# obc-v2_CM4-FUNCTION.net
KiCad netlist of a schematic drawn in Altium Designer
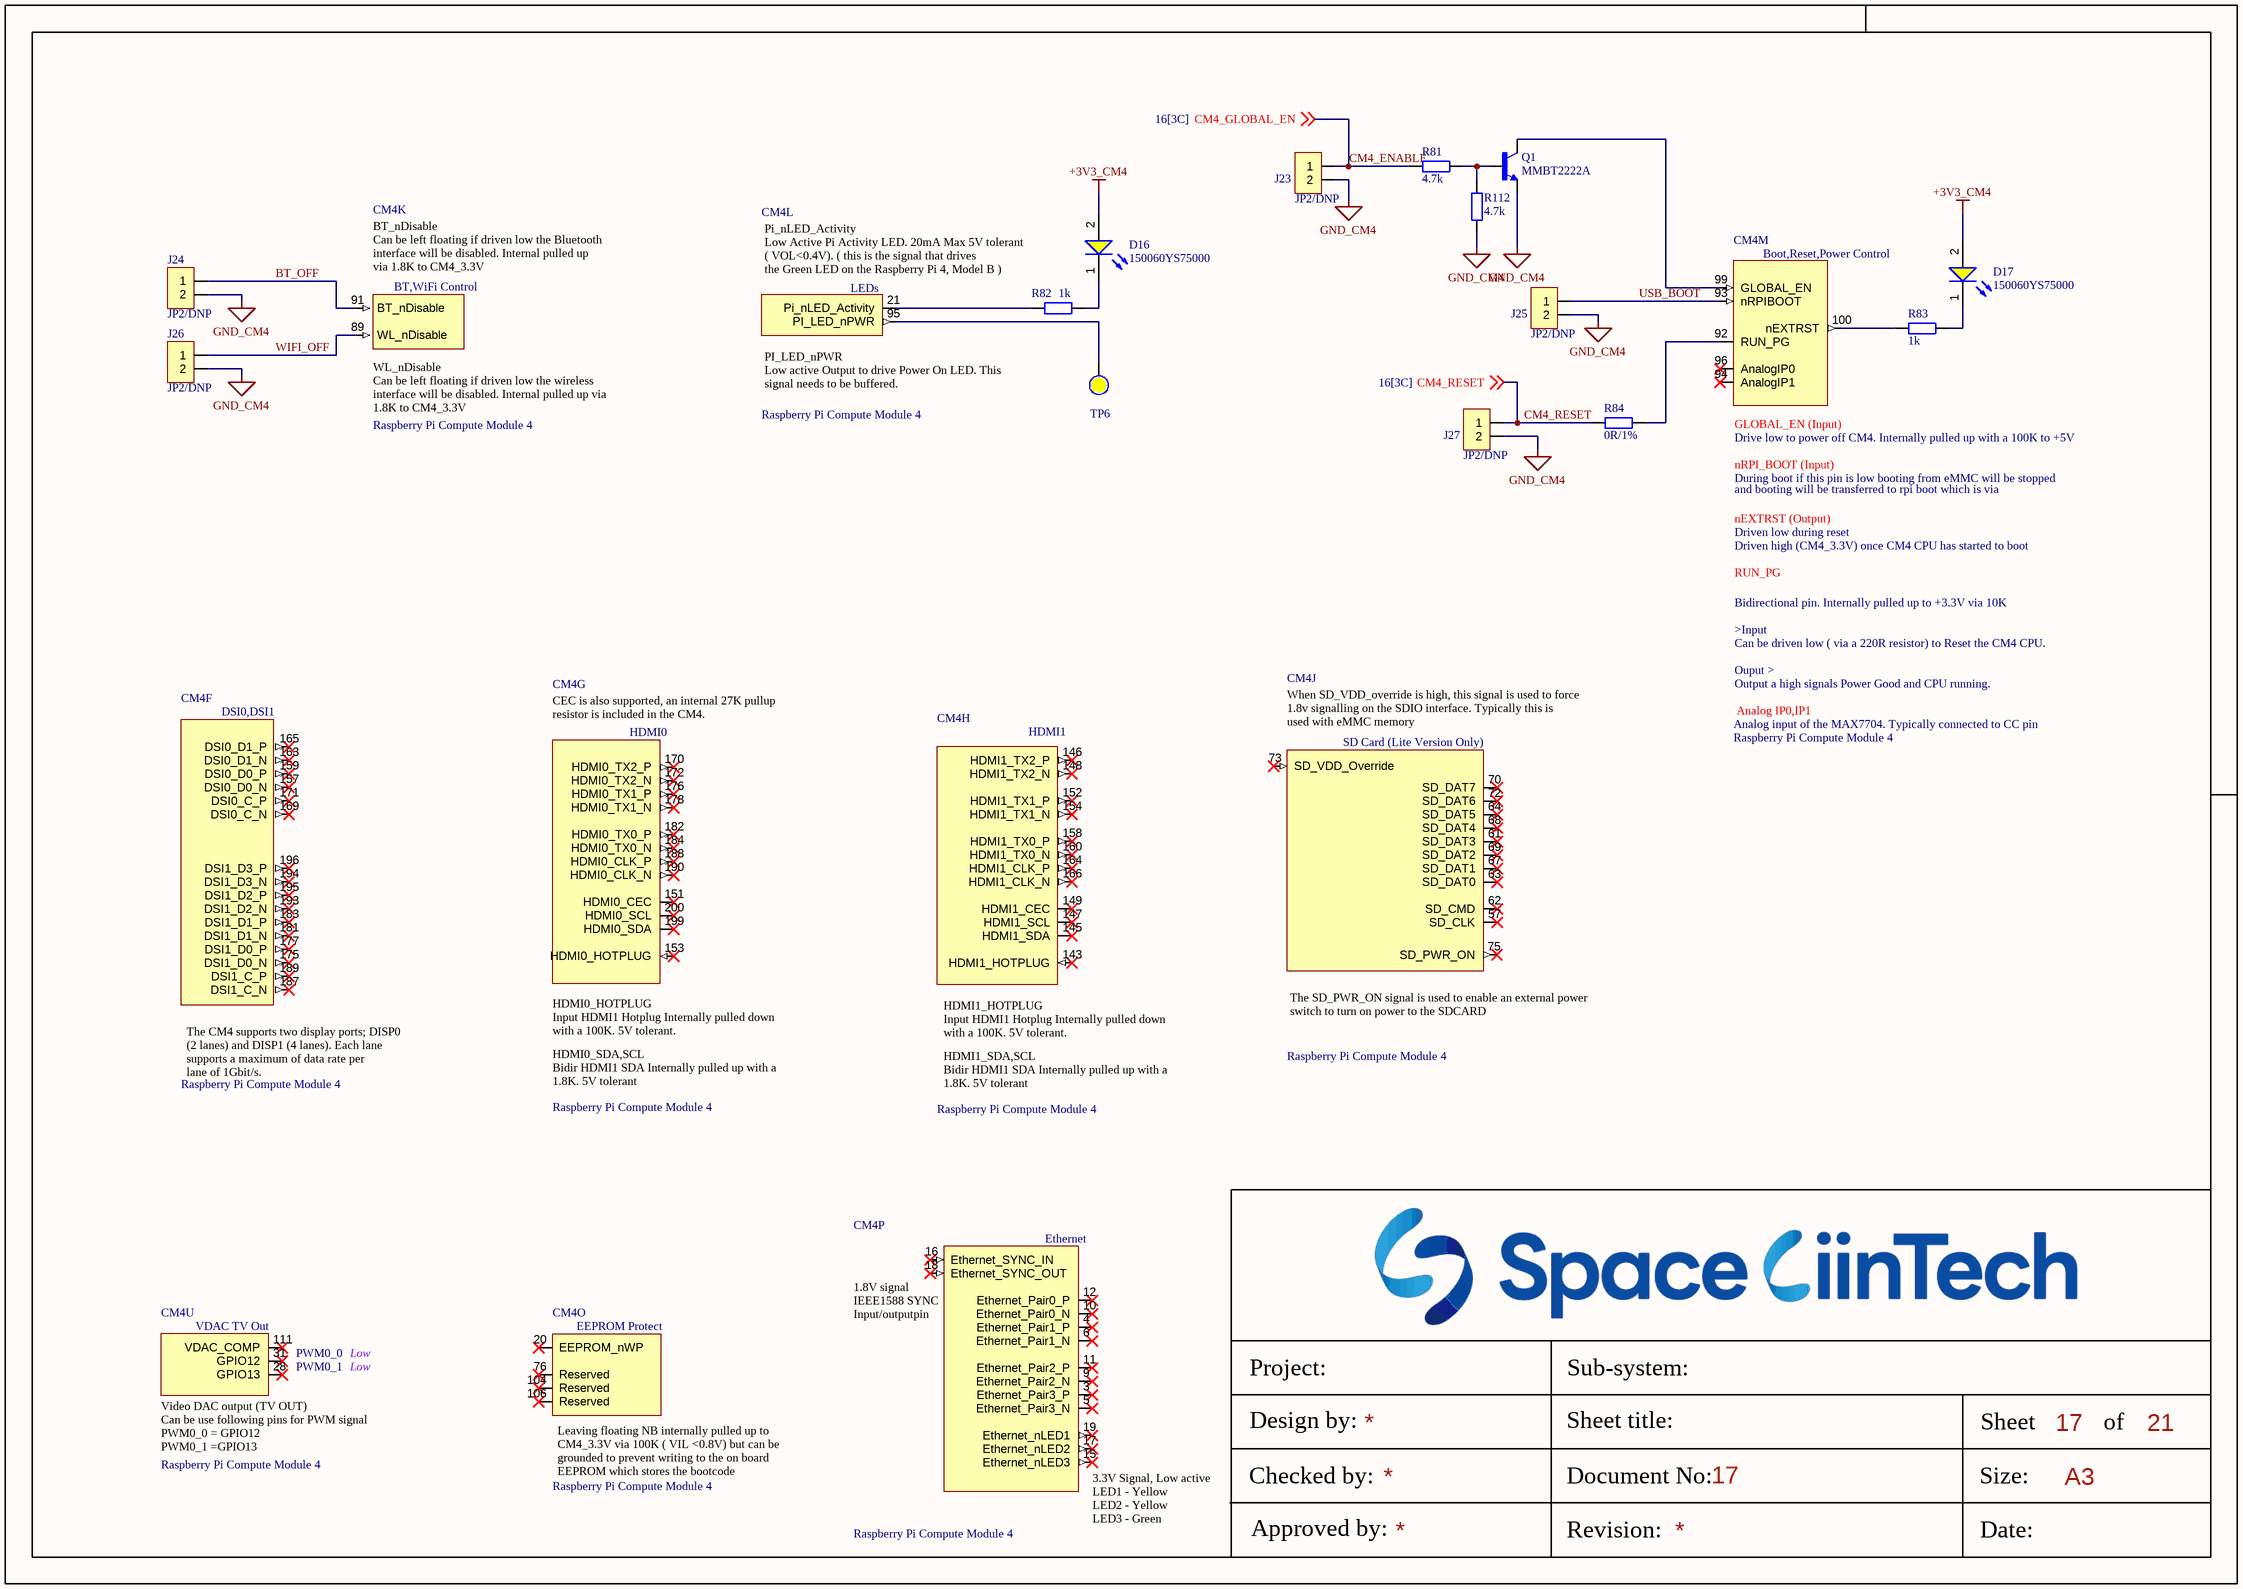
[diagram p0: obc-v2_CM4-FUNCTION.SchDoc]

(export (version "E")
  (design (tool "Eeschema 10.0.6"))
  (components
    (comp (ref "CM4")
      (value "Raspberry Pi Compute Module 4")
      (footprint "CM4-DF40HC(3.0)-100DS-0.4v_3mm_1.5mm")
      (description "Raspberry Pi Compute Module 4 by Amornthep Phunsin")
      (libsource (lib "CM4") (part "CM4"))
    )
    (comp (ref "D16")
      (value "150060YS75000")
      (footprint "WL-SMCW_0603_150060xx75000")
      (description "LED YELLOW CLEAR 0603 SMD")
      (libsource (lib "Altium Content Vault") (part "LED_Yellow_2A-1K"))
    )
    (comp (ref "D17")
      (value "150060YS75000")
      (footprint "WL-SMCW_0603_150060xx75000")
      (description "LED YELLOW CLEAR 0603 SMD")
      (libsource (lib "Altium Content Vault") (part "LED_Yellow_2A-1K"))
    )
    (comp (ref "J23")
      (value "JP2/DNP")
      (footprint "JP2-D1T")
      (description "WR-PHD 2.54 mm Angled Socket Header")
      (fields
        (field (name "MANUFACTURER") "Würth Elektronik eiSos GmbH")
        (field (name "PARTNO") "613002143121")
        (field (name "CREATED BY") "Karrer Zheng")
      )
      (libsource (lib "TechMT.VN_Lib") (part "JP2"))
    )
    (comp (ref "J24")
      (value "JP2/DNP")
      (footprint "JP2-D1T")
      (description "WR-PHD 2.54 mm Angled Socket Header")
      (fields
        (field (name "MANUFACTURER") "Würth Elektronik eiSos GmbH")
        (field (name "PARTNO") "613002143121")
        (field (name "CREATED BY") "Karrer Zheng")
      )
      (libsource (lib "TechMT.VN_Lib") (part "JP2"))
    )
    (comp (ref "J25")
      (value "JP2/DNP")
      (footprint "JP2-D1T")
      (description "WR-PHD 2.54 mm Angled Socket Header")
      (fields
        (field (name "MANUFACTURER") "Würth Elektronik eiSos GmbH")
        (field (name "PARTNO") "613002143121")
        (field (name "CREATED BY") "Karrer Zheng")
      )
      (libsource (lib "TechMT.VN_Lib") (part "JP2"))
    )
    (comp (ref "J26")
      (value "JP2/DNP")
      (footprint "JP2-D1T")
      (description "WR-PHD 2.54 mm Angled Socket Header")
      (fields
        (field (name "MANUFACTURER") "Würth Elektronik eiSos GmbH")
        (field (name "PARTNO") "613002143121")
        (field (name "CREATED BY") "Karrer Zheng")
      )
      (libsource (lib "TechMT.VN_Lib") (part "JP2"))
    )
    (comp (ref "J27")
      (value "JP2/DNP")
      (footprint "JP2-D1T")
      (description "WR-PHD 2.54 mm Angled Socket Header")
      (fields
        (field (name "MANUFACTURER") "Würth Elektronik eiSos GmbH")
        (field (name "PARTNO") "613002143121")
        (field (name "CREATED BY") "Karrer Zheng")
      )
      (libsource (lib "TechMT.VN_Lib") (part "JP2"))
    )
    (comp (ref "Q1")
      (value "MMBT2222A")
      (footprint "SOT95P240X120-3N")
      (description "BJT, SOT-23, 40V, 600mA, NPN, 0.25W, 150°C")
      (fields (field (name "MF") "Diotec Semiconductor"))
      (libsource (lib "obc_ver2") (part "MMBT2222A"))
    )
    (comp (ref "R81")
      (value "4.7k")
      (footprint "RES_C_1608X60")
      (description "RES")
      (libsource (lib "Altium_Lib_by_KhueNguyenCreator") (part "Tro 0603 1% 10k"))
    )
    (comp (ref "R82")
      (value "1k")
      (footprint "RES_C_1608X60")
      (description "RES")
      (libsource (lib "Altium_Lib_by_KhueNguyenCreator") (part "Tro 0603 1% 10k"))
    )
    (comp (ref "R83")
      (value "1k")
      (footprint "RES_C_1608X60")
      (description "RES")
      (libsource (lib "Altium_Lib_by_KhueNguyenCreator") (part "Tro 0603 1% 10k"))
    )
    (comp (ref "R84")
      (value "0R/1%")
      (footprint "RES_C_1608X60")
      (description "RES")
      (libsource (lib "Altium_Lib_by_KhueNguyenCreator") (part "Tro 0603 1% 10k"))
    )
    (comp (ref "R112")
      (value "4.7k")
      (footprint "RES_C_1608X60")
      (description "RES")
      (libsource (lib "Altium_Lib_by_KhueNguyenCreator") (part "Tro 0603 1% 10k"))
    )
    (comp (ref "TP6")
      (value "~")
      (footprint "Test Point 1 Side")
      (description "Test Point")
      (libsource (lib "BYTECH_HW_LIB_2019 (1)") (part "Test Point"))
    )
  )
  (nets
    (net (code "1") (name "+3V3_CM4") (class "Default")
      (node (ref "D16") (pin "2") (pinfunction "A_2") (pintype "passive"))
      (node (ref "D17") (pin "2") (pinfunction "A_2") (pintype "passive"))
    )
    (net (code "2") (name "/BT_OFF") (class "Default")
      (node (ref "CM4") (pin "91") (pinfunction "BT_nDisable_91") (pintype "input"))
      (node (ref "J24") (pin "1") (pinfunction "1_1") (pintype "passive"))
    )
    (net (code "3") (name "/USB_BOOT") (class "Default")
      (node (ref "CM4") (pin "93") (pinfunction "nRPIBOOT_93") (pintype "input"))
      (node (ref "J25") (pin "1") (pinfunction "1_1") (pintype "passive"))
    )
    (net (code "4") (name "/WIFI_OFF") (class "Default")
      (node (ref "CM4") (pin "89") (pinfunction "WL_nDisable_89") (pintype "input"))
      (node (ref "J26") (pin "1") (pinfunction "1_1") (pintype "passive"))
    )
    (net (code "5") (name "CM4_GLOBAL_EN") (class "Default")
      (node (ref "J23") (pin "1") (pinfunction "1_1") (pintype "passive"))
      (node (ref "R81") (pin "2") (pinfunction "2_2") (pintype "passive"))
    )
    (net (code "6") (name "CM4_RESET") (class "Default")
      (node (ref "J27") (pin "1") (pinfunction "1_1") (pintype "passive"))
      (node (ref "R84") (pin "2") (pinfunction "2_2") (pintype "passive"))
    )
    (net (code "7") (name "GND_CM4") (class "Default")
      (node (ref "J23") (pin "2") (pinfunction "2_2") (pintype "passive"))
      (node (ref "J24") (pin "2") (pinfunction "2_2") (pintype "passive"))
      (node (ref "J25") (pin "2") (pinfunction "2_2") (pintype "passive"))
      (node (ref "J26") (pin "2") (pinfunction "2_2") (pintype "passive"))
      (node (ref "J27") (pin "2") (pinfunction "2_2") (pintype "passive"))
      (node (ref "Q1") (pin "2") (pinfunction "E_2") (pintype "passive"))
      (node (ref "R112") (pin "2") (pinfunction "2_2") (pintype "passive"))
    )
    (net (code "8") (name "Net-(CM4L-PI_LED_nPWR)") (class "Default")
      (node (ref "CM4") (pin "95") (pinfunction "PI_LED_nPWR_95") (pintype "output"))
      (node (ref "TP6") (pin "0") (pinfunction "0_0") (pintype "passive"))
    )
    (net (code "9") (name "Net-(CM4L-Pi_nLED_Activity)") (class "Default")
      (node (ref "CM4") (pin "21") (pinfunction "Pi_nLED_Activity_21") (pintype "open_collector"))
      (node (ref "R82") (pin "2") (pinfunction "2_2") (pintype "passive"))
    )
    (net (code "10") (name "Net-(CM4M-GLOBAL_EN)") (class "Default")
      (node (ref "CM4") (pin "99") (pinfunction "GLOBAL_EN_99") (pintype "input"))
      (node (ref "Q1") (pin "3") (pinfunction "C_3") (pintype "passive"))
    )
    (net (code "11") (name "Net-(CM4M-RUN_PG)") (class "Default")
      (node (ref "CM4") (pin "92") (pinfunction "RUN_PG_92") (pintype "passive"))
      (node (ref "R84") (pin "1") (pinfunction "1_1") (pintype "passive"))
    )
    (net (code "12") (name "Net-(CM4M-nEXTRST)") (class "Default")
      (node (ref "CM4") (pin "100") (pinfunction "nEXTRST_100") (pintype "output"))
      (node (ref "R83") (pin "2") (pinfunction "2_2") (pintype "passive"))
    )
    (net (code "13") (name "Net-(D16-K)") (class "Default")
      (node (ref "D16") (pin "1") (pinfunction "K_1") (pintype "passive"))
      (node (ref "R82") (pin "1") (pinfunction "1_1") (pintype "passive"))
    )
    (net (code "14") (name "Net-(D17-K)") (class "Default")
      (node (ref "D17") (pin "1") (pinfunction "K_1") (pintype "passive"))
      (node (ref "R83") (pin "1") (pinfunction "1_1") (pintype "passive"))
    )
    (net (code "15") (name "Net-(Q1-B)") (class "Default")
      (node (ref "Q1") (pin "1") (pinfunction "B_1") (pintype "passive"))
      (node (ref "R112") (pin "1") (pinfunction "1_1") (pintype "passive"))
      (node (ref "R81") (pin "1") (pinfunction "1_1") (pintype "passive"))
    )
    (net (code "16") (name "unconnected-(CM4F-DSI0_C_N-Pad169)") (class "Default")
      (node (ref "CM4") (pin "169") (pinfunction "DSI0_C_N_169") (pintype "output+no_connect"))
    )
    (net (code "17") (name "unconnected-(CM4F-DSI0_C_P-Pad171)") (class "Default")
      (node (ref "CM4") (pin "171") (pinfunction "DSI0_C_P_171") (pintype "output+no_connect"))
    )
    (net (code "18") (name "unconnected-(CM4F-DSI0_D0_N-Pad157)") (class "Default")
      (node (ref "CM4") (pin "157") (pinfunction "DSI0_D0_N_157") (pintype "output+no_connect"))
    )
    (net (code "19") (name "unconnected-(CM4F-DSI0_D0_P-Pad159)") (class "Default")
      (node (ref "CM4") (pin "159") (pinfunction "DSI0_D0_P_159") (pintype "output+no_connect"))
    )
    (net (code "20") (name "unconnected-(CM4F-DSI0_D1_N-Pad163)") (class "Default")
      (node (ref "CM4") (pin "163") (pinfunction "DSI0_D1_N_163") (pintype "output+no_connect"))
    )
    (net (code "21") (name "unconnected-(CM4F-DSI0_D1_P-Pad165)") (class "Default")
      (node (ref "CM4") (pin "165") (pinfunction "DSI0_D1_P_165") (pintype "output+no_connect"))
    )
    (net (code "22") (name "unconnected-(CM4F-DSI1_C_N-Pad187)") (class "Default")
      (node (ref "CM4") (pin "187") (pinfunction "DSI1_C_N_187") (pintype "output+no_connect"))
    )
    (net (code "23") (name "unconnected-(CM4F-DSI1_C_P-Pad189)") (class "Default")
      (node (ref "CM4") (pin "189") (pinfunction "DSI1_C_P_189") (pintype "output+no_connect"))
    )
    (net (code "24") (name "unconnected-(CM4F-DSI1_D0_N-Pad175)") (class "Default")
      (node (ref "CM4") (pin "175") (pinfunction "DSI1_D0_N_175") (pintype "output+no_connect"))
    )
    (net (code "25") (name "unconnected-(CM4F-DSI1_D0_P-Pad177)") (class "Default")
      (node (ref "CM4") (pin "177") (pinfunction "DSI1_D0_P_177") (pintype "output+no_connect"))
    )
    (net (code "26") (name "unconnected-(CM4F-DSI1_D1_N-Pad181)") (class "Default")
      (node (ref "CM4") (pin "181") (pinfunction "DSI1_D1_N_181") (pintype "output+no_connect"))
    )
    (net (code "27") (name "unconnected-(CM4F-DSI1_D1_P-Pad183)") (class "Default")
      (node (ref "CM4") (pin "183") (pinfunction "DSI1_D1_P_183") (pintype "output+no_connect"))
    )
    (net (code "28") (name "unconnected-(CM4F-DSI1_D2_N-Pad193)") (class "Default")
      (node (ref "CM4") (pin "193") (pinfunction "DSI1_D2_N_193") (pintype "output+no_connect"))
    )
    (net (code "29") (name "unconnected-(CM4F-DSI1_D2_P-Pad195)") (class "Default")
      (node (ref "CM4") (pin "195") (pinfunction "DSI1_D2_P_195") (pintype "output+no_connect"))
    )
    (net (code "30") (name "unconnected-(CM4F-DSI1_D3_N-Pad194)") (class "Default")
      (node (ref "CM4") (pin "194") (pinfunction "DSI1_D3_N_194") (pintype "output+no_connect"))
    )
    (net (code "31") (name "unconnected-(CM4F-DSI1_D3_P-Pad196)") (class "Default")
      (node (ref "CM4") (pin "196") (pinfunction "DSI1_D3_P_196") (pintype "output+no_connect"))
    )
    (net (code "32") (name "unconnected-(CM4G-HDMI0_CEC-Pad151)") (class "Default")
      (node (ref "CM4") (pin "151") (pinfunction "HDMI0_CEC_151") (pintype "open_collector+no_connect"))
    )
    (net (code "33") (name "unconnected-(CM4G-HDMI0_CLK_N-Pad190)") (class "Default")
      (node (ref "CM4") (pin "190") (pinfunction "HDMI0_CLK_N_190") (pintype "output+no_connect"))
    )
    (net (code "34") (name "unconnected-(CM4G-HDMI0_CLK_P-Pad188)") (class "Default")
      (node (ref "CM4") (pin "188") (pinfunction "HDMI0_CLK_P_188") (pintype "output+no_connect"))
    )
    (net (code "35") (name "unconnected-(CM4G-HDMI0_HOTPLUG-Pad153)") (class "Default")
      (node (ref "CM4") (pin "153") (pinfunction "HDMI0_HOTPLUG_153") (pintype "input+no_connect"))
    )
    (net (code "36") (name "unconnected-(CM4G-HDMI0_SCL-Pad200)") (class "Default")
      (node (ref "CM4") (pin "200") (pinfunction "HDMI0_SCL_200") (pintype "open_collector+no_connect"))
    )
    (net (code "37") (name "unconnected-(CM4G-HDMI0_SDA-Pad199)") (class "Default")
      (node (ref "CM4") (pin "199") (pinfunction "HDMI0_SDA_199") (pintype "bidirectional+no_connect"))
    )
    (net (code "38") (name "unconnected-(CM4G-HDMI0_TX0_N-Pad184)") (class "Default")
      (node (ref "CM4") (pin "184") (pinfunction "HDMI0_TX0_N_184") (pintype "output+no_connect"))
    )
    (net (code "39") (name "unconnected-(CM4G-HDMI0_TX0_P-Pad182)") (class "Default")
      (node (ref "CM4") (pin "182") (pinfunction "HDMI0_TX0_P_182") (pintype "output+no_connect"))
    )
    (net (code "40") (name "unconnected-(CM4G-HDMI0_TX1_N-Pad178)") (class "Default")
      (node (ref "CM4") (pin "178") (pinfunction "HDMI0_TX1_N_178") (pintype "output+no_connect"))
    )
    (net (code "41") (name "unconnected-(CM4G-HDMI0_TX1_P-Pad176)") (class "Default")
      (node (ref "CM4") (pin "176") (pinfunction "HDMI0_TX1_P_176") (pintype "output+no_connect"))
    )
    (net (code "42") (name "unconnected-(CM4G-HDMI0_TX2_N-Pad172)") (class "Default")
      (node (ref "CM4") (pin "172") (pinfunction "HDMI0_TX2_N_172") (pintype "output+no_connect"))
    )
    (net (code "43") (name "unconnected-(CM4G-HDMI0_TX2_P-Pad170)") (class "Default")
      (node (ref "CM4") (pin "170") (pinfunction "HDMI0_TX2_P_170") (pintype "output+no_connect"))
    )
    (net (code "44") (name "unconnected-(CM4H-HDMI1_CEC-Pad149)") (class "Default")
      (node (ref "CM4") (pin "149") (pinfunction "HDMI1_CEC_149") (pintype "open_collector+no_connect"))
    )
    (net (code "45") (name "unconnected-(CM4H-HDMI1_CLK_N-Pad166)") (class "Default")
      (node (ref "CM4") (pin "166") (pinfunction "HDMI1_CLK_N_166") (pintype "output+no_connect"))
    )
    (net (code "46") (name "unconnected-(CM4H-HDMI1_CLK_P-Pad164)") (class "Default")
      (node (ref "CM4") (pin "164") (pinfunction "HDMI1_CLK_P_164") (pintype "output+no_connect"))
    )
    (net (code "47") (name "unconnected-(CM4H-HDMI1_HOTPLUG-Pad143)") (class "Default")
      (node (ref "CM4") (pin "143") (pinfunction "HDMI1_HOTPLUG_143") (pintype "input+no_connect"))
    )
    (net (code "48") (name "unconnected-(CM4H-HDMI1_SCL-Pad147)") (class "Default")
      (node (ref "CM4") (pin "147") (pinfunction "HDMI1_SCL_147") (pintype "open_collector+no_connect"))
    )
    (net (code "49") (name "unconnected-(CM4H-HDMI1_SDA-Pad145)") (class "Default")
      (node (ref "CM4") (pin "145") (pinfunction "HDMI1_SDA_145") (pintype "bidirectional+no_connect"))
    )
    (net (code "50") (name "unconnected-(CM4H-HDMI1_TX0_N-Pad160)") (class "Default")
      (node (ref "CM4") (pin "160") (pinfunction "HDMI1_TX0_N_160") (pintype "output+no_connect"))
    )
    (net (code "51") (name "unconnected-(CM4H-HDMI1_TX0_P-Pad158)") (class "Default")
      (node (ref "CM4") (pin "158") (pinfunction "HDMI1_TX0_P_158") (pintype "output+no_connect"))
    )
    (net (code "52") (name "unconnected-(CM4H-HDMI1_TX1_N-Pad154)") (class "Default")
      (node (ref "CM4") (pin "154") (pinfunction "HDMI1_TX1_N_154") (pintype "output+no_connect"))
    )
    (net (code "53") (name "unconnected-(CM4H-HDMI1_TX1_P-Pad152)") (class "Default")
      (node (ref "CM4") (pin "152") (pinfunction "HDMI1_TX1_P_152") (pintype "output+no_connect"))
    )
    (net (code "54") (name "unconnected-(CM4H-HDMI1_TX2_N-Pad148)") (class "Default")
      (node (ref "CM4") (pin "148") (pinfunction "HDMI1_TX2_N_148") (pintype "output+no_connect"))
    )
    (net (code "55") (name "unconnected-(CM4H-HDMI1_TX2_P-Pad146)") (class "Default")
      (node (ref "CM4") (pin "146") (pinfunction "HDMI1_TX2_P_146") (pintype "output+no_connect"))
    )
    (net (code "56") (name "unconnected-(CM4J-SD_CLK-Pad57)") (class "Default")
      (node (ref "CM4") (pin "57") (pinfunction "SD_CLK_57") (pintype "passive+no_connect"))
    )
    (net (code "57") (name "unconnected-(CM4J-SD_CMD-Pad62)") (class "Default")
      (node (ref "CM4") (pin "62") (pinfunction "SD_CMD_62") (pintype "passive+no_connect"))
    )
    (net (code "58") (name "unconnected-(CM4J-SD_DAT0-Pad63)") (class "Default")
      (node (ref "CM4") (pin "63") (pinfunction "SD_DAT0_63") (pintype "passive+no_connect"))
    )
    (net (code "59") (name "unconnected-(CM4J-SD_DAT1-Pad67)") (class "Default")
      (node (ref "CM4") (pin "67") (pinfunction "SD_DAT1_67") (pintype "passive+no_connect"))
    )
    (net (code "60") (name "unconnected-(CM4J-SD_DAT2-Pad69)") (class "Default")
      (node (ref "CM4") (pin "69") (pinfunction "SD_DAT2_69") (pintype "passive+no_connect"))
    )
    (net (code "61") (name "unconnected-(CM4J-SD_DAT3-Pad61)") (class "Default")
      (node (ref "CM4") (pin "61") (pinfunction "SD_DAT3_61") (pintype "passive+no_connect"))
    )
    (net (code "62") (name "unconnected-(CM4J-SD_DAT4-Pad68)") (class "Default")
      (node (ref "CM4") (pin "68") (pinfunction "SD_DAT4_68") (pintype "passive"))
    )
    (net (code "63") (name "unconnected-(CM4J-SD_DAT5-Pad64)") (class "Default")
      (node (ref "CM4") (pin "64") (pinfunction "SD_DAT5_64") (pintype "passive+no_connect"))
    )
    (net (code "64") (name "unconnected-(CM4J-SD_DAT6-Pad72)") (class "Default")
      (node (ref "CM4") (pin "72") (pinfunction "SD_DAT6_72") (pintype "passive+no_connect"))
    )
    (net (code "65") (name "unconnected-(CM4J-SD_DAT7-Pad70)") (class "Default")
      (node (ref "CM4") (pin "70") (pinfunction "SD_DAT7_70") (pintype "passive+no_connect"))
    )
    (net (code "66") (name "unconnected-(CM4J-SD_PWR_ON-Pad75)") (class "Default")
      (node (ref "CM4") (pin "75") (pinfunction "SD_PWR_ON_75") (pintype "output+no_connect"))
    )
    (net (code "67") (name "unconnected-(CM4J-SD_VDD_Override-Pad73)") (class "Default")
      (node (ref "CM4") (pin "73") (pinfunction "SD_VDD_Override_73") (pintype "input+no_connect"))
    )
    (net (code "68") (name "unconnected-(CM4M-AnalogIP0-Pad96)") (class "Default")
      (node (ref "CM4") (pin "96") (pinfunction "AnalogIP0_96") (pintype "passive+no_connect"))
    )
    (net (code "69") (name "unconnected-(CM4M-AnalogIP1-Pad94)") (class "Default")
      (node (ref "CM4") (pin "94") (pinfunction "AnalogIP1_94") (pintype "passive+no_connect"))
    )
    (net (code "70") (name "unconnected-(CM4O-EEPROM_nWP-Pad20)") (class "Default")
      (node (ref "CM4") (pin "20") (pinfunction "EEPROM_nWP_20") (pintype "passive+no_connect"))
    )
    (net (code "71") (name "unconnected-(CM4O-Reserved-Pad76)") (class "Default")
      (node (ref "CM4") (pin "76") (pinfunction "Reserved_76") (pintype "passive+no_connect"))
    )
    (net (code "72") (name "unconnected-(CM4O-Reserved-Pad104)") (class "Default")
      (node (ref "CM4") (pin "104") (pinfunction "Reserved_104") (pintype "passive+no_connect"))
    )
    (net (code "73") (name "unconnected-(CM4O-Reserved-Pad106)") (class "Default")
      (node (ref "CM4") (pin "106") (pinfunction "Reserved_106") (pintype "passive+no_connect"))
    )
    (net (code "74") (name "unconnected-(CM4P-Ethernet_Pair0_N-Pad10)") (class "Default")
      (node (ref "CM4") (pin "10") (pinfunction "Ethernet_Pair0_N_10") (pintype "passive+no_connect"))
    )
    (net (code "75") (name "unconnected-(CM4P-Ethernet_Pair0_P-Pad12)") (class "Default")
      (node (ref "CM4") (pin "12") (pinfunction "Ethernet_Pair0_P_12") (pintype "passive+no_connect"))
    )
    (net (code "76") (name "unconnected-(CM4P-Ethernet_Pair1_N-Pad6)") (class "Default")
      (node (ref "CM4") (pin "6") (pinfunction "Ethernet_Pair1_N_6") (pintype "passive+no_connect"))
    )
    (net (code "77") (name "unconnected-(CM4P-Ethernet_Pair1_P-Pad4)") (class "Default")
      (node (ref "CM4") (pin "4") (pinfunction "Ethernet_Pair1_P_4") (pintype "passive+no_connect"))
    )
    (net (code "78") (name "unconnected-(CM4P-Ethernet_Pair2_N-Pad9)") (class "Default")
      (node (ref "CM4") (pin "9") (pinfunction "Ethernet_Pair2_N_9") (pintype "passive+no_connect"))
    )
    (net (code "79") (name "unconnected-(CM4P-Ethernet_Pair2_P-Pad11)") (class "Default")
      (node (ref "CM4") (pin "11") (pinfunction "Ethernet_Pair2_P_11") (pintype "passive+no_connect"))
    )
    (net (code "80") (name "unconnected-(CM4P-Ethernet_Pair3_N-Pad5)") (class "Default")
      (node (ref "CM4") (pin "5") (pinfunction "Ethernet_Pair3_N_5") (pintype "passive+no_connect"))
    )
    (net (code "81") (name "unconnected-(CM4P-Ethernet_Pair3_P-Pad3)") (class "Default")
      (node (ref "CM4") (pin "3") (pinfunction "Ethernet_Pair3_P_3") (pintype "passive+no_connect"))
    )
    (net (code "82") (name "unconnected-(CM4P-Ethernet_SYNC_IN-Pad16)") (class "Default")
      (node (ref "CM4") (pin "16") (pinfunction "Ethernet_SYNC_IN_16") (pintype "input+no_connect"))
    )
    (net (code "83") (name "unconnected-(CM4P-Ethernet_SYNC_OUT-Pad18)") (class "Default")
      (node (ref "CM4") (pin "18") (pinfunction "Ethernet_SYNC_OUT_18") (pintype "input+no_connect"))
    )
    (net (code "84") (name "unconnected-(CM4P-Ethernet_nLED1-Pad19)") (class "Default")
      (node (ref "CM4") (pin "19") (pinfunction "Ethernet_nLED1_19") (pintype "output+no_connect"))
    )
    (net (code "85") (name "unconnected-(CM4P-Ethernet_nLED2-Pad17)") (class "Default")
      (node (ref "CM4") (pin "17") (pinfunction "Ethernet_nLED2_17") (pintype "output+no_connect"))
    )
    (net (code "86") (name "unconnected-(CM4P-Ethernet_nLED3-Pad15)") (class "Default")
      (node (ref "CM4") (pin "15") (pinfunction "Ethernet_nLED3_15") (pintype "output+no_connect"))
    )
    (net (code "87") (name "unconnected-(CM4U-GPIO12-Pad31)") (class "Default")
      (node (ref "CM4") (pin "31") (pinfunction "GPIO12_31") (pintype "passive+no_connect"))
    )
    (net (code "88") (name "unconnected-(CM4U-GPIO13-Pad28)") (class "Default")
      (node (ref "CM4") (pin "28") (pinfunction "GPIO13_28") (pintype "passive+no_connect"))
    )
    (net (code "89") (name "unconnected-(CM4U-VDAC_COMP-Pad111)") (class "Default")
      (node (ref "CM4") (pin "111") (pinfunction "VDAC_COMP_111") (pintype "passive+no_connect"))
    )
  )
)
